# Gateway_-_Particle_Boron_LTE_Shield.net
KiCad netlist of a schematic drawn in Altium Designer
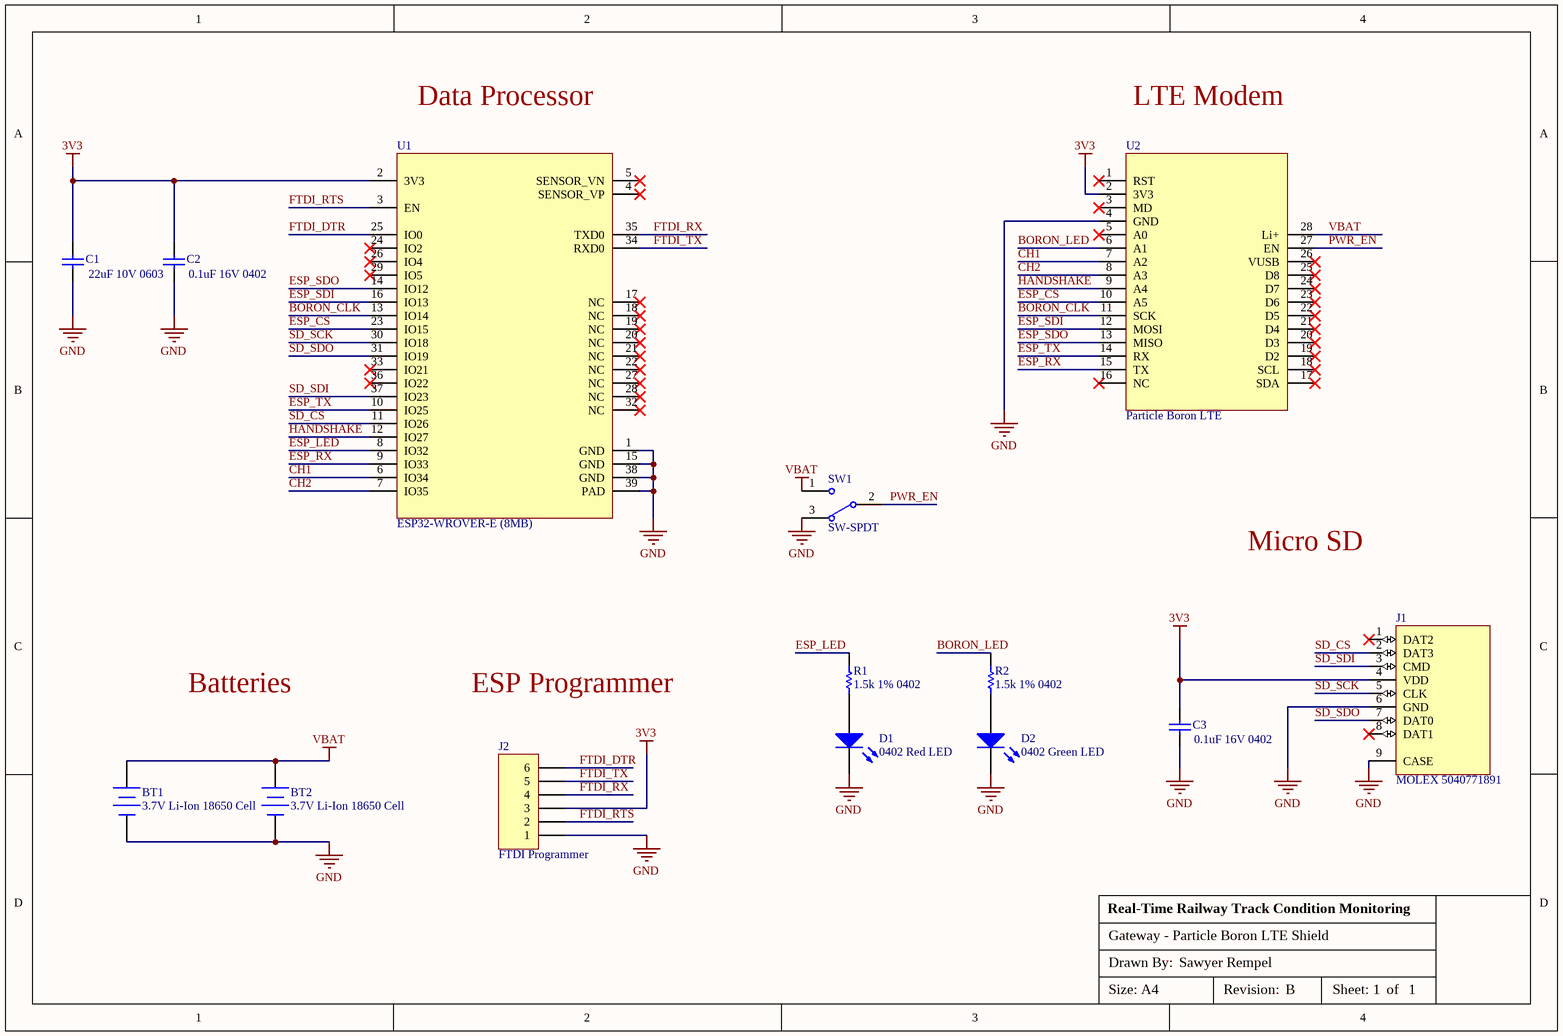
[diagram p0: Gateway - Particle Boron LTE Shield.SchDoc]

(export (version "E")
  (design (tool "Eeschema 10.0.6"))
  (components
    (comp (ref "BT1")
      (value "3.7V Li-Ion 18650 Cell")
      (footprint "18650 Battery Clip")
      (description "Multicell Battery")
      (libsource (lib "Miscellaneous Devices") (part "Battery"))
    )
    (comp (ref "BT2")
      (value "3.7V Li-Ion 18650 Cell")
      (footprint "18650 Battery Clip")
      (description "Multicell Battery")
      (libsource (lib "Miscellaneous Devices") (part "Battery"))
    )
    (comp (ref "C1")
      (value "22uF 10V 0603")
      (footprint "0603 CAP")
      (description "Capacitor")
      (libsource (lib "Miscellaneous Devices") (part "Cap"))
    )
    (comp (ref "C2")
      (value "0.1uF 16V 0402")
      (footprint "0402 CAP")
      (description "Capacitor")
      (libsource (lib "Miscellaneous Devices") (part "Cap"))
    )
    (comp (ref "C3")
      (value "0.1uF 16V 0402")
      (footprint "0402 CAP")
      (description "Capacitor")
      (libsource (lib "Miscellaneous Devices") (part "Cap"))
    )
    (comp (ref "D1")
      (value "0402 Red LED")
      (footprint "GREEN 0402 LED")
      (libsource (lib "Miscellaneous Devices") (part "LED0"))
    )
    (comp (ref "D2")
      (value "0402 Green LED")
      (footprint "GREEN 0402 LED")
      (libsource (lib "Miscellaneous Devices") (part "LED0"))
    )
    (comp (ref "J1")
      (value "MOLEX 5040771891")
      (footprint "MOLEX 5040771891")
      (libsource (lib "G02 Library") (part "MOLEX 5040771891"))
    )
    (comp (ref "J2")
      (value "FTDI Programmer")
      (footprint "PPTC061LFBN-RC")
      (description "Header, 6-Pin")
      (libsource (lib "Miscellaneous Connectors") (part "Header 6"))
    )
    (comp (ref "R1")
      (value "1.5k 1% 0402")
      (footprint "0402 RES")
      (description "Resistor")
      (libsource (lib "Miscellaneous Devices") (part "Res1"))
    )
    (comp (ref "R2")
      (value "1.5k 1% 0402")
      (footprint "0402 RES")
      (description "Resistor")
      (libsource (lib "Miscellaneous Devices") (part "Res1"))
    )
    (comp (ref "SW1")
      (value "SW-SPDT")
      (footprint "EG1218")
      (description "SPDT Subminiature Toggle Switch, Right Angle Mounting, Vertical Actuation")
      (fields (field (name "PUBLISHER") "Altium Limited"))
      (libsource (lib "Miscellaneous Devices") (part "SW-SPDT"))
    )
    (comp (ref "U1")
      (value "ESP32-WROVER-E (8MB)")
      (footprint "ESP32-WROVER-E (8MB)")
      (libsource (lib "G02 Library") (part "ESP32-WROVER-E (8MB)"))
    )
    (comp (ref "U2")
      (value "Particle Boron LTE")
      (footprint "Particle Boron LTE")
      (libsource (lib "G02 Library") (part "Particle Boron LTE"))
    )
  )
  (nets
    (net (code "1") (name "/BORON_CLK") (class "Default")
      (node (ref "U1") (pin "13") (pinfunction "IO14_13") (pintype "passive"))
      (node (ref "U2") (pin "11") (pinfunction "SCK_11") (pintype "passive"))
    )
    (net (code "2") (name "/BORON_LED") (class "Default")
      (node (ref "R2") (pin "2") (pinfunction "2_2") (pintype "passive"))
      (node (ref "U2") (pin "6") (pinfunction "A1_6") (pintype "passive"))
    )
    (net (code "3") (name "/CH1") (class "Default")
      (node (ref "U1") (pin "6") (pinfunction "IO34_6") (pintype "passive"))
      (node (ref "U2") (pin "7") (pinfunction "A2_7") (pintype "passive"))
    )
    (net (code "4") (name "/CH2") (class "Default")
      (node (ref "U1") (pin "7") (pinfunction "IO35_7") (pintype "passive"))
      (node (ref "U2") (pin "8") (pinfunction "A3_8") (pintype "passive"))
    )
    (net (code "5") (name "/ESP_CS") (class "Default")
      (node (ref "U1") (pin "23") (pinfunction "IO15_23") (pintype "passive"))
      (node (ref "U2") (pin "10") (pinfunction "A5_10") (pintype "passive"))
    )
    (net (code "6") (name "/ESP_LED") (class "Default")
      (node (ref "R1") (pin "2") (pinfunction "2_2") (pintype "passive"))
      (node (ref "U1") (pin "8") (pinfunction "IO32_8") (pintype "passive"))
    )
    (net (code "7") (name "/ESP_RX") (class "Default")
      (node (ref "U1") (pin "9") (pinfunction "IO33_9") (pintype "passive"))
      (node (ref "U2") (pin "15") (pinfunction "TX_15") (pintype "passive"))
    )
    (net (code "8") (name "/ESP_SDI") (class "Default")
      (node (ref "U1") (pin "16") (pinfunction "IO13_16") (pintype "passive"))
      (node (ref "U2") (pin "12") (pinfunction "MOSI_12") (pintype "passive"))
    )
    (net (code "9") (name "/ESP_SDO") (class "Default")
      (node (ref "U1") (pin "14") (pinfunction "IO12_14") (pintype "passive"))
      (node (ref "U2") (pin "13") (pinfunction "MISO_13") (pintype "passive"))
    )
    (net (code "10") (name "/ESP_TX") (class "Default")
      (node (ref "U1") (pin "10") (pinfunction "IO25_10") (pintype "passive"))
      (node (ref "U2") (pin "14") (pinfunction "RX_14") (pintype "passive"))
    )
    (net (code "11") (name "/FTDI_DTR") (class "Default")
      (node (ref "J2") (pin "6") (pinfunction "6_6") (pintype "passive"))
      (node (ref "U1") (pin "25") (pinfunction "IO0_25") (pintype "passive"))
    )
    (net (code "12") (name "/FTDI_RTS") (class "Default")
      (node (ref "J2") (pin "2") (pinfunction "2_2") (pintype "passive"))
      (node (ref "U1") (pin "3") (pinfunction "EN_3") (pintype "passive"))
    )
    (net (code "13") (name "/FTDI_RX") (class "Default")
      (node (ref "J2") (pin "4") (pinfunction "4_4") (pintype "passive"))
      (node (ref "U1") (pin "35") (pinfunction "TXD0_35") (pintype "passive"))
    )
    (net (code "14") (name "/FTDI_TX") (class "Default")
      (node (ref "J2") (pin "5") (pinfunction "5_5") (pintype "passive"))
      (node (ref "U1") (pin "34") (pinfunction "RXD0_34") (pintype "passive"))
    )
    (net (code "15") (name "/HANDSHAKE") (class "Default")
      (node (ref "U1") (pin "12") (pinfunction "IO27_12") (pintype "passive"))
      (node (ref "U2") (pin "9") (pinfunction "A4_9") (pintype "passive"))
    )
    (net (code "16") (name "/PWR_EN") (class "Default")
      (node (ref "SW1") (pin "2") (pinfunction "2_2") (pintype "passive"))
      (node (ref "U2") (pin "27") (pinfunction "EN_27") (pintype "passive"))
    )
    (net (code "17") (name "/SD_CS") (class "Default")
      (node (ref "J1") (pin "2") (pinfunction "DAT3_2") (pintype "bidirectional"))
      (node (ref "U1") (pin "11") (pinfunction "IO26_11") (pintype "passive"))
    )
    (net (code "18") (name "/SD_SCK") (class "Default")
      (node (ref "J1") (pin "5") (pinfunction "CLK_5") (pintype "bidirectional"))
      (node (ref "U1") (pin "30") (pinfunction "IO18_30") (pintype "passive"))
    )
    (net (code "19") (name "/SD_SDI") (class "Default")
      (node (ref "J1") (pin "3") (pinfunction "CMD_3") (pintype "bidirectional"))
      (node (ref "U1") (pin "37") (pinfunction "IO23_37") (pintype "passive"))
    )
    (net (code "20") (name "/SD_SDO") (class "Default")
      (node (ref "J1") (pin "7") (pinfunction "DAT0_7") (pintype "bidirectional"))
      (node (ref "U1") (pin "31") (pinfunction "IO19_31") (pintype "passive"))
    )
    (net (code "21") (name "3V3") (class "Default")
      (node (ref "C1") (pin "1") (pinfunction "1_1") (pintype "passive"))
      (node (ref "C2") (pin "1") (pinfunction "1_1") (pintype "passive"))
      (node (ref "C3") (pin "1") (pinfunction "1_1") (pintype "passive"))
      (node (ref "J1") (pin "4") (pinfunction "VDD_4") (pintype "power_in"))
      (node (ref "J2") (pin "3") (pinfunction "3_3") (pintype "passive"))
      (node (ref "U1") (pin "2") (pinfunction "3V3_2") (pintype "passive"))
      (node (ref "U2") (pin "2") (pinfunction "3V3_2") (pintype "passive"))
    )
    (net (code "22") (name "GND") (class "Default")
      (node (ref "BT1") (pin "2") (pinfunction "-_2") (pintype "passive"))
      (node (ref "BT2") (pin "2") (pinfunction "-_2") (pintype "passive"))
      (node (ref "C1") (pin "2") (pinfunction "2_2") (pintype "passive"))
      (node (ref "C2") (pin "2") (pinfunction "2_2") (pintype "passive"))
      (node (ref "C3") (pin "2") (pinfunction "2_2") (pintype "passive"))
      (node (ref "D1") (pin "2") (pinfunction "K_2") (pintype "passive"))
      (node (ref "D2") (pin "2") (pinfunction "K_2") (pintype "passive"))
      (node (ref "J1") (pin "6") (pinfunction "GND_6") (pintype "power_in"))
      (node (ref "J1") (pin "9") (pinfunction "CASE_9") (pintype "power_in"))
      (node (ref "J2") (pin "1") (pinfunction "1_1") (pintype "passive"))
      (node (ref "SW1") (pin "3") (pinfunction "3_3") (pintype "passive"))
      (node (ref "U1") (pin "1") (pinfunction "GND_1") (pintype "passive"))
      (node (ref "U1") (pin "15") (pinfunction "GND_15") (pintype "passive"))
      (node (ref "U1") (pin "38") (pinfunction "GND_38") (pintype "passive"))
      (node (ref "U1") (pin "39") (pinfunction "PAD_39") (pintype "passive"))
      (node (ref "U2") (pin "4") (pinfunction "GND_4") (pintype "passive"))
    )
    (net (code "23") (name "Net-(D1-A)") (class "Default")
      (node (ref "D1") (pin "1") (pinfunction "A_1") (pintype "passive"))
      (node (ref "R1") (pin "1") (pinfunction "1_1") (pintype "passive"))
    )
    (net (code "24") (name "Net-(D2-A)") (class "Default")
      (node (ref "D2") (pin "1") (pinfunction "A_1") (pintype "passive"))
      (node (ref "R2") (pin "1") (pinfunction "1_1") (pintype "passive"))
    )
    (net (code "25") (name "VBAT") (class "Default")
      (node (ref "BT1") (pin "1") (pinfunction "+_1") (pintype "passive"))
      (node (ref "BT2") (pin "1") (pinfunction "+_1") (pintype "passive"))
      (node (ref "SW1") (pin "1") (pinfunction "1_1") (pintype "passive"))
      (node (ref "U2") (pin "28") (pinfunction "Li+_28") (pintype "passive"))
    )
    (net (code "26") (name "unconnected-(J1-DAT1-Pad8)") (class "Default")
      (node (ref "J1") (pin "8") (pinfunction "DAT1_8") (pintype "bidirectional+no_connect"))
    )
    (net (code "27") (name "unconnected-(J1-DAT2-Pad1)") (class "Default")
      (node (ref "J1") (pin "1") (pinfunction "DAT2_1") (pintype "bidirectional+no_connect"))
    )
    (net (code "28") (name "unconnected-(U1-IO2-Pad24)") (class "Default")
      (node (ref "U1") (pin "24") (pinfunction "IO2_24") (pintype "passive+no_connect"))
    )
    (net (code "29") (name "unconnected-(U1-IO4-Pad26)") (class "Default")
      (node (ref "U1") (pin "26") (pinfunction "IO4_26") (pintype "passive+no_connect"))
    )
    (net (code "30") (name "unconnected-(U1-IO5-Pad29)") (class "Default")
      (node (ref "U1") (pin "29") (pinfunction "IO5_29") (pintype "passive+no_connect"))
    )
    (net (code "31") (name "unconnected-(U1-IO21-Pad33)") (class "Default")
      (node (ref "U1") (pin "33") (pinfunction "IO21_33") (pintype "passive+no_connect"))
    )
    (net (code "32") (name "unconnected-(U1-IO22-Pad36)") (class "Default")
      (node (ref "U1") (pin "36") (pinfunction "IO22_36") (pintype "passive+no_connect"))
    )
    (net (code "33") (name "unconnected-(U1-NC-Pad17)") (class "Default")
      (node (ref "U1") (pin "17") (pinfunction "NC_17") (pintype "passive+no_connect"))
    )
    (net (code "34") (name "unconnected-(U1-NC-Pad18)") (class "Default")
      (node (ref "U1") (pin "18") (pinfunction "NC_18") (pintype "passive+no_connect"))
    )
    (net (code "35") (name "unconnected-(U1-NC-Pad19)") (class "Default")
      (node (ref "U1") (pin "19") (pinfunction "NC_19") (pintype "passive+no_connect"))
    )
    (net (code "36") (name "unconnected-(U1-NC-Pad20)") (class "Default")
      (node (ref "U1") (pin "20") (pinfunction "NC_20") (pintype "passive+no_connect"))
    )
    (net (code "37") (name "unconnected-(U1-NC-Pad21)") (class "Default")
      (node (ref "U1") (pin "21") (pinfunction "NC_21") (pintype "passive+no_connect"))
    )
    (net (code "38") (name "unconnected-(U1-NC-Pad22)") (class "Default")
      (node (ref "U1") (pin "22") (pinfunction "NC_22") (pintype "passive+no_connect"))
    )
    (net (code "39") (name "unconnected-(U1-NC-Pad27)") (class "Default")
      (node (ref "U1") (pin "27") (pinfunction "NC_27") (pintype "passive+no_connect"))
    )
    (net (code "40") (name "unconnected-(U1-NC-Pad28)") (class "Default")
      (node (ref "U1") (pin "28") (pinfunction "NC_28") (pintype "passive+no_connect"))
    )
    (net (code "41") (name "unconnected-(U1-NC-Pad32)") (class "Default")
      (node (ref "U1") (pin "32") (pinfunction "NC_32") (pintype "passive+no_connect"))
    )
    (net (code "42") (name "unconnected-(U1-SENSOR_VN-Pad5)") (class "Default")
      (node (ref "U1") (pin "5") (pinfunction "SENSOR_VN_5") (pintype "passive+no_connect"))
    )
    (net (code "43") (name "unconnected-(U1-SENSOR_VP-Pad4)") (class "Default")
      (node (ref "U1") (pin "4") (pinfunction "SENSOR_VP_4") (pintype "passive+no_connect"))
    )
    (net (code "44") (name "unconnected-(U2-A0-Pad5)") (class "Default")
      (node (ref "U2") (pin "5") (pinfunction "A0_5") (pintype "passive+no_connect"))
    )
    (net (code "45") (name "unconnected-(U2-D2-Pad19)") (class "Default")
      (node (ref "U2") (pin "19") (pinfunction "D2_19") (pintype "passive+no_connect"))
    )
    (net (code "46") (name "unconnected-(U2-D3-Pad20)") (class "Default")
      (node (ref "U2") (pin "20") (pinfunction "D3_20") (pintype "passive+no_connect"))
    )
    (net (code "47") (name "unconnected-(U2-D4-Pad21)") (class "Default")
      (node (ref "U2") (pin "21") (pinfunction "D4_21") (pintype "passive+no_connect"))
    )
    (net (code "48") (name "unconnected-(U2-D5-Pad22)") (class "Default")
      (node (ref "U2") (pin "22") (pinfunction "D5_22") (pintype "passive+no_connect"))
    )
    (net (code "49") (name "unconnected-(U2-D6-Pad23)") (class "Default")
      (node (ref "U2") (pin "23") (pinfunction "D6_23") (pintype "passive+no_connect"))
    )
    (net (code "50") (name "unconnected-(U2-D7-Pad24)") (class "Default")
      (node (ref "U2") (pin "24") (pinfunction "D7_24") (pintype "passive+no_connect"))
    )
    (net (code "51") (name "unconnected-(U2-D8-Pad25)") (class "Default")
      (node (ref "U2") (pin "25") (pinfunction "D8_25") (pintype "passive+no_connect"))
    )
    (net (code "52") (name "unconnected-(U2-MD-Pad3)") (class "Default")
      (node (ref "U2") (pin "3") (pinfunction "MD_3") (pintype "passive+no_connect"))
    )
    (net (code "53") (name "unconnected-(U2-NC-Pad16)") (class "Default")
      (node (ref "U2") (pin "16") (pinfunction "NC_16") (pintype "passive+no_connect"))
    )
    (net (code "54") (name "unconnected-(U2-RST-Pad1)") (class "Default")
      (node (ref "U2") (pin "1") (pinfunction "RST_1") (pintype "passive+no_connect"))
    )
    (net (code "55") (name "unconnected-(U2-SCL-Pad18)") (class "Default")
      (node (ref "U2") (pin "18") (pinfunction "SCL_18") (pintype "passive+no_connect"))
    )
    (net (code "56") (name "unconnected-(U2-SDA-Pad17)") (class "Default")
      (node (ref "U2") (pin "17") (pinfunction "SDA_17") (pintype "passive+no_connect"))
    )
    (net (code "57") (name "unconnected-(U2-VUSB-Pad26)") (class "Default")
      (node (ref "U2") (pin "26") (pinfunction "VUSB_26") (pintype "passive+no_connect"))
    )
  )
)
